# cellSwitcher_ni_mh_V6.net
KiCad netlist of a schematic drawn in EAGLE
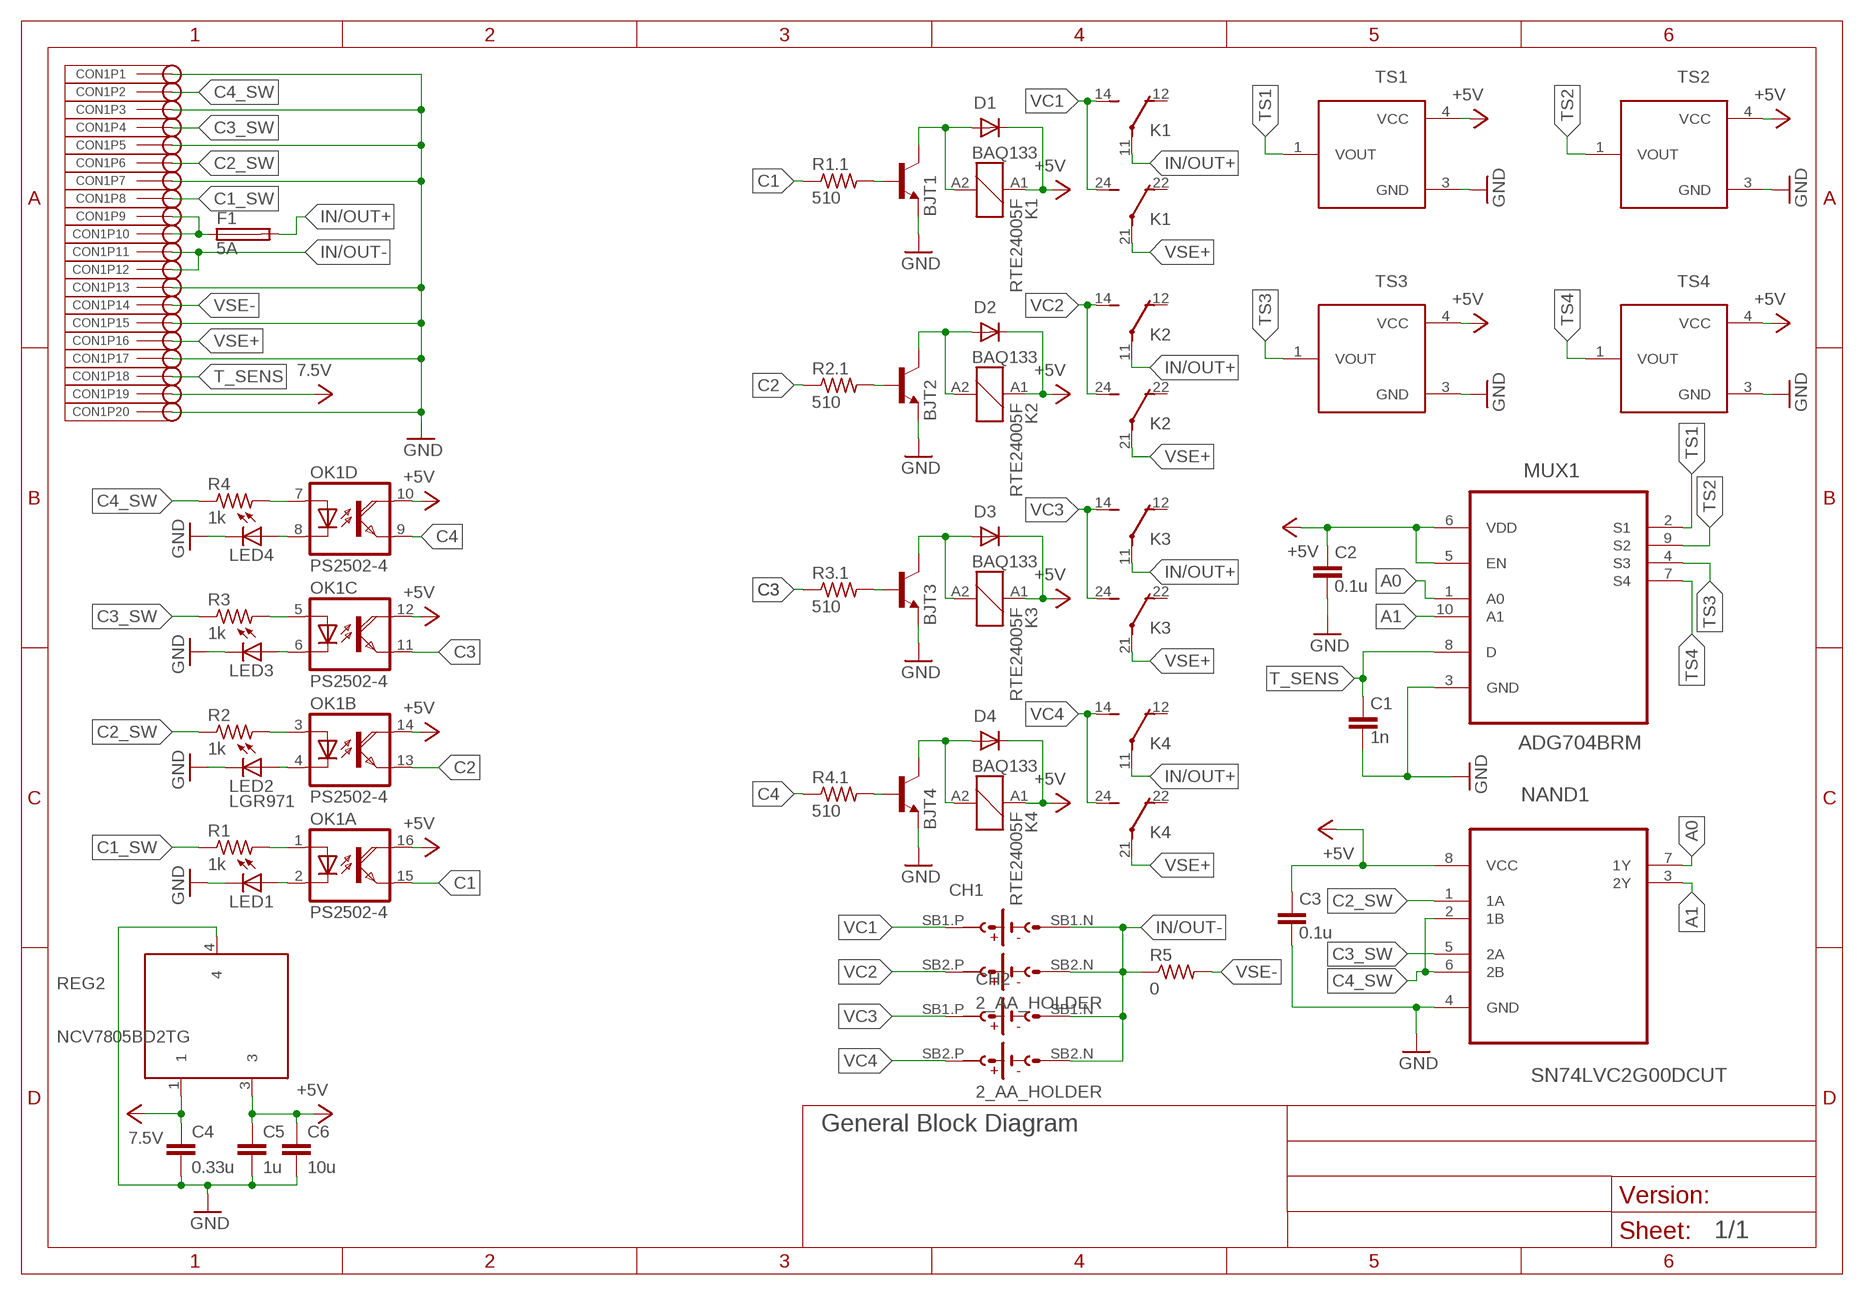
[diagram p0: schematic, sheet 1]

(export (version "E")
  (design (tool "Eeschema 10.0.6"))
  (components
    (comp (ref "BJT1")
      (value "BC818K-40")
      (footprint "eagle-import:SOT-23")
      (libsource (lib "eagle-import") (part "BC818K-40"))
    )
    (comp (ref "BJT2")
      (value "BC818K-40")
      (footprint "eagle-import:SOT-23")
      (libsource (lib "eagle-import") (part "BC818K-40"))
    )
    (comp (ref "BJT3")
      (value "BC818K-40")
      (footprint "eagle-import:SOT-23")
      (libsource (lib "eagle-import") (part "BC818K-40"))
    )
    (comp (ref "BJT4")
      (value "BC818K-40")
      (footprint "eagle-import:SOT-23")
      (libsource (lib "eagle-import") (part "BC818K-40"))
    )
    (comp (ref "C1")
      (value "1n")
      (footprint "eagle-import:C0603")
      (libsource (lib "eagle-import") (part "NONPOL_CAP-0603"))
    )
    (comp (ref "C2")
      (value "0.1u")
      (footprint "eagle-import:C0603")
      (libsource (lib "eagle-import") (part "NONPOL_CAP-0603"))
    )
    (comp (ref "C3")
      (value "0.1u")
      (footprint "eagle-import:C0603")
      (libsource (lib "eagle-import") (part "NONPOL_CAP-0603"))
    )
    (comp (ref "C4")
      (value "0.33u")
      (footprint "eagle-import:C0603")
      (libsource (lib "eagle-import") (part "NONPOL_CAP-0603"))
    )
    (comp (ref "C5")
      (value "1u")
      (footprint "eagle-import:C0603")
      (libsource (lib "eagle-import") (part "NONPOL_CAP-0603"))
    )
    (comp (ref "C6")
      (value "10u")
      (footprint "eagle-import:C0603")
      (libsource (lib "eagle-import") (part "NONPOL_CAP-0603"))
    )
    (comp (ref "CH1")
      (value "2_AA_HOLDER")
      (footprint "eagle-import:2_AA_HOLDER")
      (libsource (lib "eagle-import") (part "2_AA_HOLDER"))
    )
    (comp (ref "CH2")
      (value "2_AA_HOLDER")
      (footprint "eagle-import:2_AA_HOLDER")
      (libsource (lib "eagle-import") (part "2_AA_HOLDER"))
    )
    (comp (ref "CON1")
      (value "TMM-110-01-F-D-RA")
      (footprint "eagle-import:TMM-110-01-F-D-RA")
      (libsource (lib "eagle-import") (part "TMM-110-01-F-D-RA"))
    )
    (comp (ref "D1")
      (value "BAQ133")
      (footprint "eagle-import:SOD08")
      (libsource (lib "eagle-import") (part "DIODE-BAQ133-GS08"))
    )
    (comp (ref "D2")
      (value "BAQ133")
      (footprint "eagle-import:SOD08")
      (libsource (lib "eagle-import") (part "DIODE-BAQ133-GS08"))
    )
    (comp (ref "D3")
      (value "BAQ133")
      (footprint "eagle-import:SOD08")
      (libsource (lib "eagle-import") (part "DIODE-BAQ133-GS08"))
    )
    (comp (ref "D4")
      (value "BAQ133")
      (footprint "eagle-import:SOD08")
      (libsource (lib "eagle-import") (part "DIODE-BAQ133-GS08"))
    )
    (comp (ref "F1")
      (value "5A")
      (footprint "eagle-import:SH22,5")
      (fields (field (name "MF") "SCHURTER") (field (name "MPN") "0031.8201"))
      (libsource (lib "eagle-import") (part "FUSEHOLDER"))
    )
    (comp (ref "K1")
      (value "RTE24005F")
      (footprint "eagle-import:RTE24005F")
      (libsource (lib "eagle-import") (part "RTE24005F"))
    )
    (comp (ref "K2")
      (value "RTE24005F")
      (footprint "eagle-import:RTE24005F")
      (libsource (lib "eagle-import") (part "RTE24005F"))
    )
    (comp (ref "K3")
      (value "RTE24005F")
      (footprint "eagle-import:RTE24005F")
      (libsource (lib "eagle-import") (part "RTE24005F"))
    )
    (comp (ref "K4")
      (value "RTE24005F")
      (footprint "eagle-import:RTE24005F")
      (libsource (lib "eagle-import") (part "RTE24005F"))
    )
    (comp (ref "LED1")
      (value "LGR971")
      (footprint "eagle-import:SML0805")
      (libsource (lib "eagle-import") (part "LGR971"))
    )
    (comp (ref "LED2")
      (value "LGR971")
      (footprint "eagle-import:SML0805")
      (libsource (lib "eagle-import") (part "LGR971"))
    )
    (comp (ref "LED3")
      (value "LGR971")
      (footprint "eagle-import:SML0805")
      (libsource (lib "eagle-import") (part "LGR971"))
    )
    (comp (ref "LED4")
      (value "LGR971")
      (footprint "eagle-import:SML0805")
      (libsource (lib "eagle-import") (part "LGR971"))
    )
    (comp (ref "MUX1")
      (value "ADG704BRM")
      (footprint "eagle-import:MSOP10")
      (fields (field (name "MPN") "ADG704BRM-REEL"))
      (libsource (lib "eagle-import") (part "ADG704BRM"))
    )
    (comp (ref "NAND1")
      (value "SN74LVC2G00DCUT")
      (footprint "eagle-import:VSSOP-8")
      (libsource (lib "eagle-import") (part "SN74LVC2G00DCUT"))
    )
    (comp (ref "OK1")
      (value "PS2502-4")
      (footprint "eagle-import:DIL16")
      (libsource (lib "eagle-import") (part "PS2502-4"))
    )
    (comp (ref "R1")
      (value "1k")
      (footprint "eagle-import:R0603")
      (libsource (lib "eagle-import") (part "RESISTOR-0603"))
    )
    (comp (ref "R1.1")
      (value "510")
      (footprint "eagle-import:R0603")
      (libsource (lib "eagle-import") (part "RESISTOR-0603"))
    )
    (comp (ref "R2")
      (value "1k")
      (footprint "eagle-import:R0603")
      (libsource (lib "eagle-import") (part "RESISTOR-0603"))
    )
    (comp (ref "R2.1")
      (value "510")
      (footprint "eagle-import:R0603")
      (libsource (lib "eagle-import") (part "RESISTOR-0603"))
    )
    (comp (ref "R3")
      (value "1k")
      (footprint "eagle-import:R0603")
      (libsource (lib "eagle-import") (part "RESISTOR-0603"))
    )
    (comp (ref "R3.1")
      (value "510")
      (footprint "eagle-import:R0603")
      (libsource (lib "eagle-import") (part "RESISTOR-0603"))
    )
    (comp (ref "R4")
      (value "1k")
      (footprint "eagle-import:R0603")
      (libsource (lib "eagle-import") (part "RESISTOR-0603"))
    )
    (comp (ref "R4.1")
      (value "510")
      (footprint "eagle-import:R0603")
      (libsource (lib "eagle-import") (part "RESISTOR-0603"))
    )
    (comp (ref "R5")
      (value "0")
      (footprint "eagle-import:R0603")
      (libsource (lib "eagle-import") (part "RESISTOR-0603"))
    )
    (comp (ref "REG2")
      (value "NCV7805BD2TG")
      (footprint "eagle-import:D2PAK-3")
      (libsource (lib "eagle-import") (part "NCV7805BD2TG"))
    )
    (comp (ref "TS1")
      (value "STLM20DD9F")
      (footprint "eagle-import:UDFN-4L")
      (libsource (lib "eagle-import") (part "STLM20DD9F"))
    )
    (comp (ref "TS2")
      (value "STLM20DD9F")
      (footprint "eagle-import:UDFN-4L")
      (libsource (lib "eagle-import") (part "STLM20DD9F"))
    )
    (comp (ref "TS3")
      (value "STLM20DD9F")
      (footprint "eagle-import:UDFN-4L")
      (libsource (lib "eagle-import") (part "STLM20DD9F"))
    )
    (comp (ref "TS4")
      (value "STLM20DD9F")
      (footprint "eagle-import:UDFN-4L")
      (libsource (lib "eagle-import") (part "STLM20DD9F"))
    )
  )
  (nets
    (net (code "1") (name "+5V") (class "Default")
      (node (ref "C2") (pin "1") (pinfunction "1_1") (pintype "passive"))
      (node (ref "C3") (pin "1") (pinfunction "1_1") (pintype "passive"))
      (node (ref "C5") (pin "1") (pinfunction "1_1") (pintype "passive"))
      (node (ref "C6") (pin "1") (pinfunction "1_1") (pintype "passive"))
      (node (ref "D1") (pin "C") (pinfunction "C_C") (pintype "passive"))
      (node (ref "D2") (pin "C") (pinfunction "C_C") (pintype "passive"))
      (node (ref "D3") (pin "C") (pinfunction "C_C") (pintype "passive"))
      (node (ref "D4") (pin "C") (pinfunction "C_C") (pintype "passive"))
      (node (ref "K1") (pin "A1") (pinfunction "1_A1") (pintype "passive"))
      (node (ref "K2") (pin "A1") (pinfunction "1_A1") (pintype "passive"))
      (node (ref "K3") (pin "A1") (pinfunction "1_A1") (pintype "passive"))
      (node (ref "K4") (pin "A1") (pinfunction "1_A1") (pintype "passive"))
      (node (ref "MUX1") (pin "5") (pinfunction "EN_5") (pintype "input"))
      (node (ref "MUX1") (pin "6") (pinfunction "VDD_6") (pintype "power_in"))
      (node (ref "NAND1") (pin "8") (pinfunction "VCC_8") (pintype "power_in"))
      (node (ref "OK1") (pin "10") (pinfunction "COL_10") (pintype "passive"))
      (node (ref "OK1") (pin "12") (pinfunction "COL_12") (pintype "passive"))
      (node (ref "OK1") (pin "14") (pinfunction "COL_14") (pintype "passive"))
      (node (ref "OK1") (pin "16") (pinfunction "COL_16") (pintype "passive"))
      (node (ref "REG2") (pin "3") (pinfunction "3_3") (pintype "bidirectional"))
      (node (ref "TS1") (pin "4") (pinfunction "VCC_4") (pintype "bidirectional"))
      (node (ref "TS2") (pin "4") (pinfunction "VCC_4") (pintype "bidirectional"))
      (node (ref "TS3") (pin "4") (pinfunction "VCC_4") (pintype "bidirectional"))
      (node (ref "TS4") (pin "4") (pinfunction "VCC_4") (pintype "bidirectional"))
    )
    (net (code "2") (name "7.5V") (class "Default")
      (node (ref "C4") (pin "1") (pinfunction "1_1") (pintype "passive"))
      (node (ref "CON1") (pin "19") (pinfunction "PIN_19") (pintype "bidirectional"))
      (node (ref "REG2") (pin "1") (pinfunction "1_1") (pintype "bidirectional"))
    )
    (net (code "3") (name "A0") (class "Default")
      (node (ref "MUX1") (pin "1") (pinfunction "A0_1") (pintype "input"))
      (node (ref "NAND1") (pin "7") (pinfunction "1Y_7") (pintype "output"))
    )
    (net (code "4") (name "A1") (class "Default")
      (node (ref "MUX1") (pin "10") (pinfunction "A1_10") (pintype "input"))
      (node (ref "NAND1") (pin "3") (pinfunction "2Y_3") (pintype "output"))
    )
    (net (code "5") (name "C1") (class "Default")
      (node (ref "OK1") (pin "15") (pinfunction "EMI_15") (pintype "passive"))
      (node (ref "R1.1") (pin "1") (pinfunction "1_1") (pintype "passive"))
    )
    (net (code "6") (name "C1_SW") (class "Default")
      (node (ref "CON1") (pin "8") (pinfunction "PIN_8") (pintype "bidirectional"))
      (node (ref "R1") (pin "1") (pinfunction "1_1") (pintype "passive"))
    )
    (net (code "7") (name "C2") (class "Default")
      (node (ref "OK1") (pin "13") (pinfunction "EMI_13") (pintype "passive"))
      (node (ref "R2.1") (pin "1") (pinfunction "1_1") (pintype "passive"))
    )
    (net (code "8") (name "C2_SW") (class "Default")
      (node (ref "CON1") (pin "6") (pinfunction "PIN_6") (pintype "bidirectional"))
      (node (ref "NAND1") (pin "1") (pinfunction "1A_1") (pintype "input"))
      (node (ref "R2") (pin "1") (pinfunction "1_1") (pintype "passive"))
    )
    (net (code "9") (name "C3") (class "Default")
      (node (ref "OK1") (pin "11") (pinfunction "EMI_11") (pintype "passive"))
      (node (ref "R3.1") (pin "1") (pinfunction "1_1") (pintype "passive"))
    )
    (net (code "10") (name "C3_SW") (class "Default")
      (node (ref "CON1") (pin "4") (pinfunction "PIN_4") (pintype "bidirectional"))
      (node (ref "NAND1") (pin "5") (pinfunction "2A_5") (pintype "input"))
      (node (ref "R3") (pin "1") (pinfunction "1_1") (pintype "passive"))
    )
    (net (code "11") (name "C4") (class "Default")
      (node (ref "OK1") (pin "9") (pinfunction "EMI_9") (pintype "passive"))
      (node (ref "R4.1") (pin "1") (pinfunction "1_1") (pintype "passive"))
    )
    (net (code "12") (name "C4_SW") (class "Default")
      (node (ref "CON1") (pin "2") (pinfunction "PIN_2") (pintype "bidirectional"))
      (node (ref "NAND1") (pin "2") (pinfunction "1B_2") (pintype "input"))
      (node (ref "NAND1") (pin "6") (pinfunction "2B_6") (pintype "input"))
      (node (ref "R4") (pin "1") (pinfunction "1_1") (pintype "passive"))
    )
    (net (code "13") (name "GND") (class "Default")
      (node (ref "BJT1") (pin "2") (pinfunction "E_2") (pintype "passive"))
      (node (ref "BJT2") (pin "2") (pinfunction "E_2") (pintype "passive"))
      (node (ref "BJT3") (pin "2") (pinfunction "E_2") (pintype "passive"))
      (node (ref "BJT4") (pin "2") (pinfunction "E_2") (pintype "passive"))
      (node (ref "C1") (pin "2") (pinfunction "2_2") (pintype "passive"))
      (node (ref "C2") (pin "2") (pinfunction "2_2") (pintype "passive"))
      (node (ref "C3") (pin "2") (pinfunction "2_2") (pintype "passive"))
      (node (ref "C4") (pin "2") (pinfunction "2_2") (pintype "passive"))
      (node (ref "C5") (pin "2") (pinfunction "2_2") (pintype "passive"))
      (node (ref "C6") (pin "2") (pinfunction "2_2") (pintype "passive"))
      (node (ref "CON1") (pin "1") (pinfunction "PIN_1") (pintype "bidirectional"))
      (node (ref "CON1") (pin "13") (pinfunction "PIN_13") (pintype "bidirectional"))
      (node (ref "CON1") (pin "15") (pinfunction "PIN_15") (pintype "bidirectional"))
      (node (ref "CON1") (pin "17") (pinfunction "PIN_17") (pintype "bidirectional"))
      (node (ref "CON1") (pin "20") (pinfunction "PIN_20") (pintype "bidirectional"))
      (node (ref "CON1") (pin "3") (pinfunction "PIN_3") (pintype "bidirectional"))
      (node (ref "CON1") (pin "5") (pinfunction "PIN_5") (pintype "bidirectional"))
      (node (ref "CON1") (pin "7") (pinfunction "PIN_7") (pintype "bidirectional"))
      (node (ref "LED1") (pin "C") (pinfunction "C_C") (pintype "passive"))
      (node (ref "LED2") (pin "C") (pinfunction "C_C") (pintype "passive"))
      (node (ref "LED3") (pin "C") (pinfunction "C_C") (pintype "passive"))
      (node (ref "LED4") (pin "C") (pinfunction "C_C") (pintype "passive"))
      (node (ref "MUX1") (pin "3") (pinfunction "GND_3") (pintype "passive"))
      (node (ref "NAND1") (pin "4") (pinfunction "GND_4") (pintype "passive"))
      (node (ref "REG2") (pin "4") (pinfunction "4_4") (pintype "bidirectional"))
      (node (ref "TS1") (pin "3") (pinfunction "GND_3") (pintype "bidirectional"))
      (node (ref "TS2") (pin "3") (pinfunction "GND_3") (pintype "bidirectional"))
      (node (ref "TS3") (pin "3") (pinfunction "GND_3") (pintype "bidirectional"))
      (node (ref "TS4") (pin "3") (pinfunction "GND_3") (pintype "bidirectional"))
    )
    (net (code "14") (name "IN{slash}OUT+") (class "Default")
      (node (ref "F1") (pin "2") (pinfunction "2_2") (pintype "passive"))
      (node (ref "K1") (pin "11") (pinfunction "COM_11") (pintype "passive"))
      (node (ref "K2") (pin "11") (pinfunction "COM_11") (pintype "passive"))
      (node (ref "K3") (pin "11") (pinfunction "COM_11") (pintype "passive"))
      (node (ref "K4") (pin "11") (pinfunction "COM_11") (pintype "passive"))
    )
    (net (code "15") (name "IN{slash}OUT-") (class "Default")
      (node (ref "CH1") (pin "SB1.N") (pinfunction "B1.N_SB1.N") (pintype "bidirectional"))
      (node (ref "CH1") (pin "SB2.N") (pinfunction "B2.N_SB2.N") (pintype "bidirectional"))
      (node (ref "CH2") (pin "SB1.N") (pinfunction "B1.N_SB1.N") (pintype "bidirectional"))
      (node (ref "CH2") (pin "SB2.N") (pinfunction "B2.N_SB2.N") (pintype "bidirectional"))
      (node (ref "CON1") (pin "11") (pinfunction "PIN_11") (pintype "bidirectional"))
      (node (ref "CON1") (pin "12") (pinfunction "PIN_12") (pintype "bidirectional"))
      (node (ref "R5") (pin "1") (pinfunction "1_1") (pintype "passive"))
    )
    (net (code "16") (name "Net-(BJT1-B)") (class "Default")
      (node (ref "BJT1") (pin "1") (pinfunction "B_1") (pintype "passive"))
      (node (ref "R1.1") (pin "2") (pinfunction "2_2") (pintype "passive"))
    )
    (net (code "17") (name "Net-(BJT1-C)") (class "Default")
      (node (ref "BJT1") (pin "3") (pinfunction "C_3") (pintype "passive"))
      (node (ref "D1") (pin "A") (pinfunction "A_A") (pintype "passive"))
      (node (ref "K1") (pin "A2") (pinfunction "2_A2") (pintype "passive"))
    )
    (net (code "18") (name "Net-(BJT2-B)") (class "Default")
      (node (ref "BJT2") (pin "1") (pinfunction "B_1") (pintype "passive"))
      (node (ref "R2.1") (pin "2") (pinfunction "2_2") (pintype "passive"))
    )
    (net (code "19") (name "Net-(BJT2-C)") (class "Default")
      (node (ref "BJT2") (pin "3") (pinfunction "C_3") (pintype "passive"))
      (node (ref "D2") (pin "A") (pinfunction "A_A") (pintype "passive"))
      (node (ref "K2") (pin "A2") (pinfunction "2_A2") (pintype "passive"))
    )
    (net (code "20") (name "Net-(BJT3-B)") (class "Default")
      (node (ref "BJT3") (pin "1") (pinfunction "B_1") (pintype "passive"))
      (node (ref "R3.1") (pin "2") (pinfunction "2_2") (pintype "passive"))
    )
    (net (code "21") (name "Net-(BJT3-C)") (class "Default")
      (node (ref "BJT3") (pin "3") (pinfunction "C_3") (pintype "passive"))
      (node (ref "D3") (pin "A") (pinfunction "A_A") (pintype "passive"))
      (node (ref "K3") (pin "A2") (pinfunction "2_A2") (pintype "passive"))
    )
    (net (code "22") (name "Net-(BJT4-B)") (class "Default")
      (node (ref "BJT4") (pin "1") (pinfunction "B_1") (pintype "passive"))
      (node (ref "R4.1") (pin "2") (pinfunction "2_2") (pintype "passive"))
    )
    (net (code "23") (name "Net-(BJT4-C)") (class "Default")
      (node (ref "BJT4") (pin "3") (pinfunction "C_3") (pintype "passive"))
      (node (ref "D4") (pin "A") (pinfunction "A_A") (pintype "passive"))
      (node (ref "K4") (pin "A2") (pinfunction "2_A2") (pintype "passive"))
    )
    (net (code "24") (name "Net-(CON1B-PIN)") (class "Default")
      (node (ref "CON1") (pin "10") (pinfunction "PIN_10") (pintype "bidirectional"))
      (node (ref "CON1") (pin "9") (pinfunction "PIN_9") (pintype "bidirectional"))
      (node (ref "F1") (pin "1") (pinfunction "1_1") (pintype "passive"))
    )
    (net (code "25") (name "Net-(OK1A-A)") (class "Default")
      (node (ref "OK1") (pin "1") (pinfunction "A_1") (pintype "passive"))
      (node (ref "R1") (pin "2") (pinfunction "2_2") (pintype "passive"))
    )
    (net (code "26") (name "Net-(OK1A-C)") (class "Default")
      (node (ref "LED1") (pin "A") (pinfunction "A_A") (pintype "passive"))
      (node (ref "OK1") (pin "2") (pinfunction "C_2") (pintype "passive"))
    )
    (net (code "27") (name "Net-(OK1B-A)") (class "Default")
      (node (ref "OK1") (pin "3") (pinfunction "A_3") (pintype "passive"))
      (node (ref "R2") (pin "2") (pinfunction "2_2") (pintype "passive"))
    )
    (net (code "28") (name "Net-(OK1B-C)") (class "Default")
      (node (ref "LED2") (pin "A") (pinfunction "A_A") (pintype "passive"))
      (node (ref "OK1") (pin "4") (pinfunction "C_4") (pintype "passive"))
    )
    (net (code "29") (name "Net-(OK1C-A)") (class "Default")
      (node (ref "OK1") (pin "5") (pinfunction "A_5") (pintype "passive"))
      (node (ref "R3") (pin "2") (pinfunction "2_2") (pintype "passive"))
    )
    (net (code "30") (name "Net-(OK1C-C)") (class "Default")
      (node (ref "LED3") (pin "A") (pinfunction "A_A") (pintype "passive"))
      (node (ref "OK1") (pin "6") (pinfunction "C_6") (pintype "passive"))
    )
    (net (code "31") (name "Net-(OK1D-A)") (class "Default")
      (node (ref "OK1") (pin "7") (pinfunction "A_7") (pintype "passive"))
      (node (ref "R4") (pin "2") (pinfunction "2_2") (pintype "passive"))
    )
    (net (code "32") (name "Net-(OK1D-C)") (class "Default")
      (node (ref "LED4") (pin "A") (pinfunction "A_A") (pintype "passive"))
      (node (ref "OK1") (pin "8") (pinfunction "C_8") (pintype "passive"))
    )
    (net (code "33") (name "TS1") (class "Default")
      (node (ref "MUX1") (pin "2") (pinfunction "S1_2") (pintype "bidirectional"))
      (node (ref "TS1") (pin "1") (pinfunction "VOUT_1") (pintype "bidirectional"))
    )
    (net (code "34") (name "TS2") (class "Default")
      (node (ref "MUX1") (pin "9") (pinfunction "S2_9") (pintype "bidirectional"))
      (node (ref "TS2") (pin "1") (pinfunction "VOUT_1") (pintype "bidirectional"))
    )
    (net (code "35") (name "TS3") (class "Default")
      (node (ref "MUX1") (pin "4") (pinfunction "S3_4") (pintype "bidirectional"))
      (node (ref "TS3") (pin "1") (pinfunction "VOUT_1") (pintype "bidirectional"))
    )
    (net (code "36") (name "TS4") (class "Default")
      (node (ref "MUX1") (pin "7") (pinfunction "S4_7") (pintype "bidirectional"))
      (node (ref "TS4") (pin "1") (pinfunction "VOUT_1") (pintype "bidirectional"))
    )
    (net (code "37") (name "T_SENS") (class "Default")
      (node (ref "C1") (pin "1") (pinfunction "1_1") (pintype "passive"))
      (node (ref "CON1") (pin "18") (pinfunction "PIN_18") (pintype "bidirectional"))
      (node (ref "MUX1") (pin "8") (pinfunction "D_8") (pintype "bidirectional"))
    )
    (net (code "38") (name "VC1") (class "Default")
      (node (ref "CH1") (pin "SB1.P") (pinfunction "B1.P_SB1.P") (pintype "bidirectional"))
      (node (ref "K1") (pin "14") (pinfunction "NO_14") (pintype "passive"))
      (node (ref "K1") (pin "24") (pinfunction "NO_24") (pintype "passive"))
    )
    (net (code "39") (name "VC2") (class "Default")
      (node (ref "CH1") (pin "SB2.P") (pinfunction "B2.P_SB2.P") (pintype "bidirectional"))
      (node (ref "K2") (pin "14") (pinfunction "NO_14") (pintype "passive"))
      (node (ref "K2") (pin "24") (pinfunction "NO_24") (pintype "passive"))
    )
    (net (code "40") (name "VC3") (class "Default")
      (node (ref "CH2") (pin "SB1.P") (pinfunction "B1.P_SB1.P") (pintype "bidirectional"))
      (node (ref "K3") (pin "14") (pinfunction "NO_14") (pintype "passive"))
      (node (ref "K3") (pin "24") (pinfunction "NO_24") (pintype "passive"))
    )
    (net (code "41") (name "VC4") (class "Default")
      (node (ref "CH2") (pin "SB2.P") (pinfunction "B2.P_SB2.P") (pintype "bidirectional"))
      (node (ref "K4") (pin "14") (pinfunction "NO_14") (pintype "passive"))
      (node (ref "K4") (pin "24") (pinfunction "NO_24") (pintype "passive"))
    )
    (net (code "42") (name "VSE+") (class "Default")
      (node (ref "CON1") (pin "16") (pinfunction "PIN_16") (pintype "bidirectional"))
      (node (ref "K1") (pin "21") (pinfunction "COM_21") (pintype "passive"))
      (node (ref "K2") (pin "21") (pinfunction "COM_21") (pintype "passive"))
      (node (ref "K3") (pin "21") (pinfunction "COM_21") (pintype "passive"))
      (node (ref "K4") (pin "21") (pinfunction "COM_21") (pintype "passive"))
    )
    (net (code "43") (name "VSE-") (class "Default")
      (node (ref "CON1") (pin "14") (pinfunction "PIN_14") (pintype "bidirectional"))
      (node (ref "R5") (pin "2") (pinfunction "2_2") (pintype "passive"))
    )
    (net (code "44") (name "unconnected-(K1B-NC-Pad12)") (class "Default")
      (node (ref "K1") (pin "12") (pinfunction "NC_12") (pintype "passive"))
    )
    (net (code "45") (name "unconnected-(K1C-NC-Pad22)") (class "Default")
      (node (ref "K1") (pin "22") (pinfunction "NC_22") (pintype "passive"))
    )
    (net (code "46") (name "unconnected-(K2B-NC-Pad12)") (class "Default")
      (node (ref "K2") (pin "12") (pinfunction "NC_12") (pintype "passive"))
    )
    (net (code "47") (name "unconnected-(K2C-NC-Pad22)") (class "Default")
      (node (ref "K2") (pin "22") (pinfunction "NC_22") (pintype "passive"))
    )
    (net (code "48") (name "unconnected-(K3B-NC-Pad12)") (class "Default")
      (node (ref "K3") (pin "12") (pinfunction "NC_12") (pintype "passive"))
    )
    (net (code "49") (name "unconnected-(K3C-NC-Pad22)") (class "Default")
      (node (ref "K3") (pin "22") (pinfunction "NC_22") (pintype "passive"))
    )
    (net (code "50") (name "unconnected-(K4B-NC-Pad12)") (class "Default")
      (node (ref "K4") (pin "12") (pinfunction "NC_12") (pintype "passive"))
    )
    (net (code "51") (name "unconnected-(K4C-NC-Pad22)") (class "Default")
      (node (ref "K4") (pin "22") (pinfunction "NC_22") (pintype "passive"))
    )
  )
)
